# Relays.net
KiCad netlist of a schematic drawn in Altium Designer
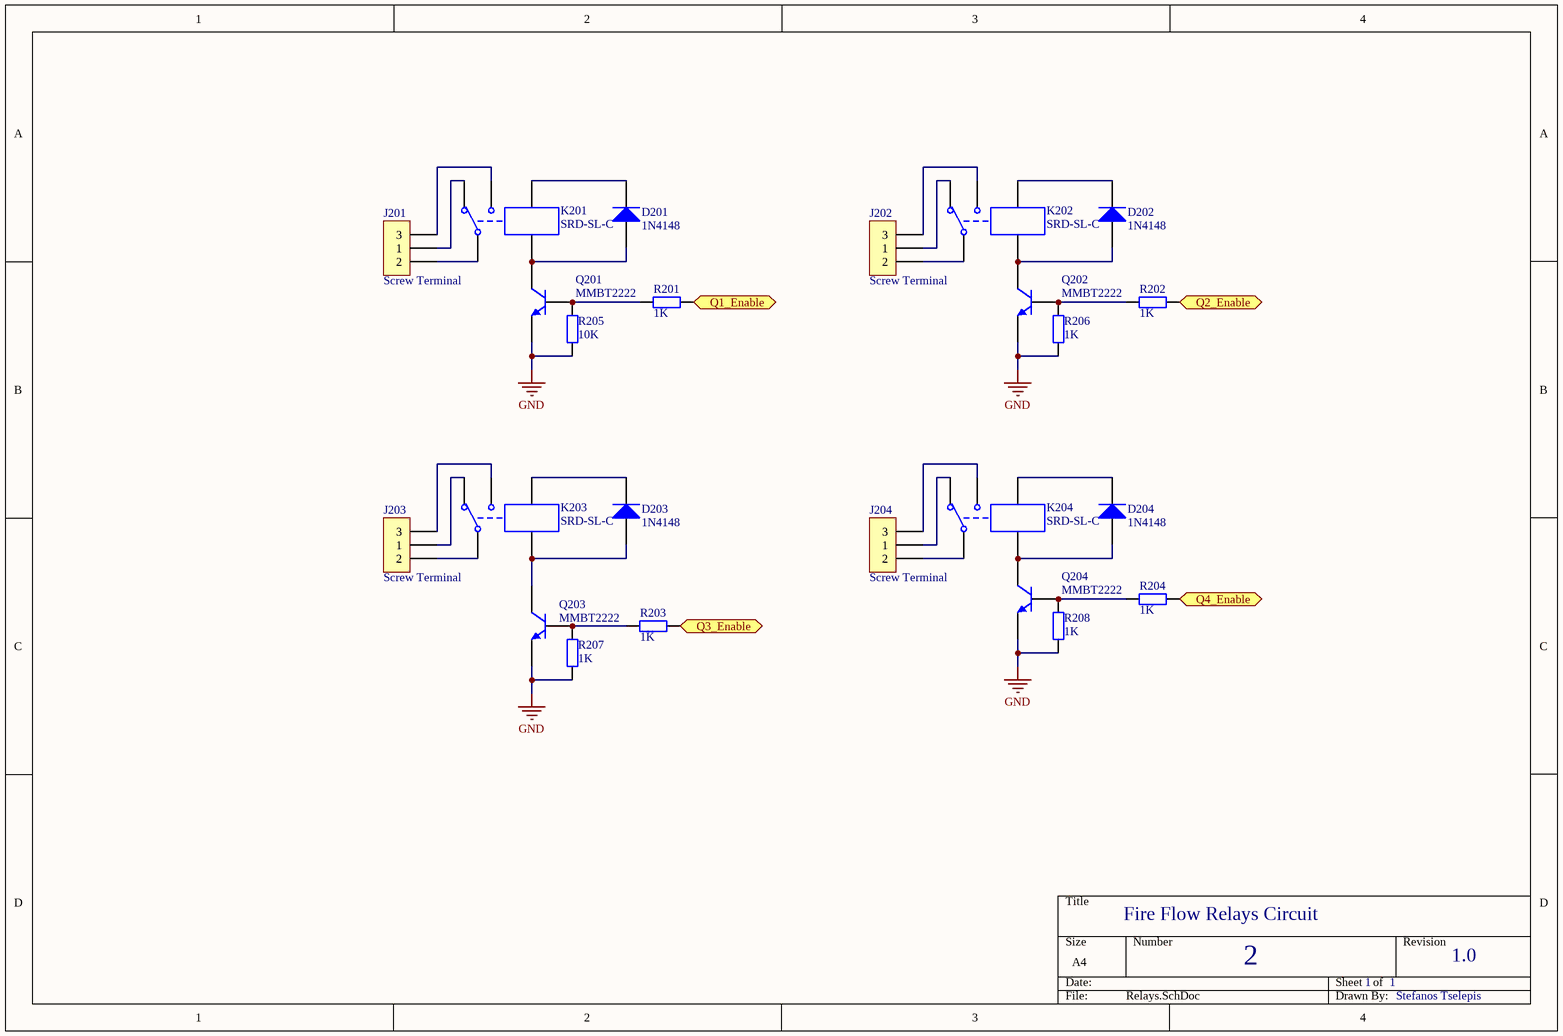
[diagram p0: Relays.SchDoc]

(export (version "E")
  (design (tool "Eeschema 10.0.6"))
  (components
    (comp (ref "D201")
      (value "1N4148")
      (footprint "CD2012-0805")
      (libsource (lib "FireFlow Lib") (part "Diode"))
    )
    (comp (ref "D202")
      (value "1N4148")
      (footprint "CD2012-0805")
      (libsource (lib "FireFlow Lib") (part "Diode"))
    )
    (comp (ref "D203")
      (value "1N4148")
      (footprint "CD2012-0805")
      (libsource (lib "FireFlow Lib") (part "Diode"))
    )
    (comp (ref "D204")
      (value "1N4148")
      (footprint "CD2012-0805")
      (libsource (lib "FireFlow Lib") (part "Diode"))
    )
    (comp (ref "J201")
      (value "Screw Terminal")
      (footprint "3pin ST")
      (description "WR-TBL Terminal block - serie 102 - 5.0mm")
      (libsource (lib "FireFlow Lib") (part "3 pin Screw Terminal"))
    )
    (comp (ref "J202")
      (value "Screw Terminal")
      (footprint "3pin ST")
      (description "WR-TBL Terminal block - serie 102 - 5.0mm")
      (libsource (lib "FireFlow Lib") (part "3 pin Screw Terminal"))
    )
    (comp (ref "J203")
      (value "Screw Terminal")
      (footprint "3pin ST")
      (description "WR-TBL Terminal block - serie 102 - 5.0mm")
      (libsource (lib "FireFlow Lib") (part "3 pin Screw Terminal"))
    )
    (comp (ref "J204")
      (value "Screw Terminal")
      (footprint "3pin ST")
      (description "WR-TBL Terminal block - serie 102 - 5.0mm")
      (libsource (lib "FireFlow Lib") (part "3 pin Screw Terminal"))
    )
    (comp (ref "K201")
      (value "SRD-SL-C")
      (footprint "SRD-SL-C")
      (libsource (lib "FireFlow") (part "Relay SRD-SL-C"))
    )
    (comp (ref "K202")
      (value "SRD-SL-C")
      (footprint "SRD-SL-C")
      (libsource (lib "FireFlow") (part "Relay SRD-SL-C"))
    )
    (comp (ref "K203")
      (value "SRD-SL-C")
      (footprint "SRD-SL-C")
      (libsource (lib "FireFlow") (part "Relay SRD-SL-C"))
    )
    (comp (ref "K204")
      (value "SRD-SL-C")
      (footprint "SRD-SL-C")
      (libsource (lib "FireFlow") (part "Relay SRD-SL-C"))
    )
    (comp (ref "Q201")
      (value "MMBT2222")
      (footprint "SO-G3")
      (description "NPN General Purpose Amplifier")
      (libsource (lib "FireFlow Lib") (part "MMBT2222"))
    )
    (comp (ref "Q202")
      (value "MMBT2222")
      (footprint "SO-G3")
      (description "NPN General Purpose Amplifier")
      (libsource (lib "FireFlow Lib") (part "MMBT2222"))
    )
    (comp (ref "Q203")
      (value "MMBT2222")
      (footprint "SO-G3")
      (description "NPN General Purpose Amplifier")
      (libsource (lib "FireFlow Lib") (part "MMBT2222"))
    )
    (comp (ref "Q204")
      (value "MMBT2222")
      (footprint "SO-G3")
      (description "NPN General Purpose Amplifier")
      (libsource (lib "FireFlow Lib") (part "MMBT2222"))
    )
    (comp (ref "R201") (value "1K") (footprint "CR2012-0805") (libsource (lib "") (part "Resistor_1")))
    (comp (ref "R202") (value "1K") (footprint "CR2012-0805") (libsource (lib "") (part "Resistor_1")))
    (comp (ref "R203") (value "1K") (footprint "CR2012-0805") (libsource (lib "") (part "Resistor_1")))
    (comp (ref "R204") (value "1K") (footprint "CR2012-0805") (libsource (lib "") (part "Resistor_1")))
    (comp (ref "R205")
      (value "10K")
      (footprint "CR2012-0805")
      (libsource (lib "FireFlow Lib") (part "Resistor"))
    )
    (comp (ref "R206")
      (value "1K")
      (footprint "CR2012-0805")
      (libsource (lib "FireFlow Lib") (part "Resistor"))
    )
    (comp (ref "R207")
      (value "1K")
      (footprint "CR2012-0805")
      (libsource (lib "FireFlow Lib") (part "Resistor"))
    )
    (comp (ref "R208")
      (value "1K")
      (footprint "CR2012-0805")
      (libsource (lib "FireFlow Lib") (part "Resistor"))
    )
  )
  (nets
    (net (code "1") (name "/Q1_Enable") (class "Default")
      (node (ref "R201") (pin "2") (pinfunction "2_2") (pintype "passive"))
    )
    (net (code "2") (name "/Q2_Enable") (class "Default")
      (node (ref "R202") (pin "2") (pinfunction "2_2") (pintype "passive"))
    )
    (net (code "3") (name "/Q3_Enable") (class "Default")
      (node (ref "R203") (pin "2") (pinfunction "2_2") (pintype "passive"))
    )
    (net (code "4") (name "/Q4_Enable") (class "Default")
      (node (ref "R204") (pin "2") (pinfunction "2_2") (pintype "passive"))
    )
    (net (code "5") (name "GND") (class "Default")
      (node (ref "Q201") (pin "2") (pinfunction "E_2") (pintype "passive"))
      (node (ref "Q202") (pin "2") (pinfunction "E_2") (pintype "passive"))
      (node (ref "Q203") (pin "2") (pinfunction "E_2") (pintype "passive"))
      (node (ref "Q204") (pin "2") (pinfunction "E_2") (pintype "passive"))
      (node (ref "R205") (pin "1") (pinfunction "1_1") (pintype "passive"))
      (node (ref "R206") (pin "1") (pinfunction "1_1") (pintype "passive"))
      (node (ref "R207") (pin "1") (pinfunction "1_1") (pintype "passive"))
      (node (ref "R208") (pin "1") (pinfunction "1_1") (pintype "passive"))
    )
    (net (code "6") (name "Net-(D201-PadK)") (class "Default")
      (node (ref "D201") (pin "K") (pinfunction "K_K") (pintype "passive"))
      (node (ref "K201") (pin "1") (pinfunction "1_1") (pintype "passive"))
    )
    (net (code "7") (name "Net-(D202-PadK)") (class "Default")
      (node (ref "D202") (pin "K") (pinfunction "K_K") (pintype "passive"))
      (node (ref "K202") (pin "1") (pinfunction "1_1") (pintype "passive"))
    )
    (net (code "8") (name "Net-(D203-PadK)") (class "Default")
      (node (ref "D203") (pin "K") (pinfunction "K_K") (pintype "passive"))
      (node (ref "K203") (pin "1") (pinfunction "1_1") (pintype "passive"))
    )
    (net (code "9") (name "Net-(D204-PadK)") (class "Default")
      (node (ref "D204") (pin "K") (pinfunction "K_K") (pintype "passive"))
      (node (ref "K204") (pin "1") (pinfunction "1_1") (pintype "passive"))
    )
    (net (code "10") (name "Net-(J201-Pad1)") (class "Default")
      (node (ref "J201") (pin "1") (pinfunction "1_1") (pintype "passive"))
      (node (ref "K201") (pin "5") (pinfunction "5_5") (pintype "passive"))
    )
    (net (code "11") (name "Net-(J201-Pad2)") (class "Default")
      (node (ref "J201") (pin "2") (pinfunction "2_2") (pintype "passive"))
      (node (ref "K201") (pin "3") (pinfunction "3_3") (pintype "passive"))
    )
    (net (code "12") (name "Net-(J201-Pad3)") (class "Default")
      (node (ref "J201") (pin "3") (pinfunction "3_3") (pintype "passive"))
      (node (ref "K201") (pin "4") (pinfunction "4_4") (pintype "passive"))
    )
    (net (code "13") (name "Net-(J202-Pad1)") (class "Default")
      (node (ref "J202") (pin "1") (pinfunction "1_1") (pintype "passive"))
      (node (ref "K202") (pin "5") (pinfunction "5_5") (pintype "passive"))
    )
    (net (code "14") (name "Net-(J202-Pad2)") (class "Default")
      (node (ref "J202") (pin "2") (pinfunction "2_2") (pintype "passive"))
      (node (ref "K202") (pin "3") (pinfunction "3_3") (pintype "passive"))
    )
    (net (code "15") (name "Net-(J202-Pad3)") (class "Default")
      (node (ref "J202") (pin "3") (pinfunction "3_3") (pintype "passive"))
      (node (ref "K202") (pin "4") (pinfunction "4_4") (pintype "passive"))
    )
    (net (code "16") (name "Net-(J203-Pad1)") (class "Default")
      (node (ref "J203") (pin "1") (pinfunction "1_1") (pintype "passive"))
      (node (ref "K203") (pin "5") (pinfunction "5_5") (pintype "passive"))
    )
    (net (code "17") (name "Net-(J203-Pad2)") (class "Default")
      (node (ref "J203") (pin "2") (pinfunction "2_2") (pintype "passive"))
      (node (ref "K203") (pin "3") (pinfunction "3_3") (pintype "passive"))
    )
    (net (code "18") (name "Net-(J203-Pad3)") (class "Default")
      (node (ref "J203") (pin "3") (pinfunction "3_3") (pintype "passive"))
      (node (ref "K203") (pin "4") (pinfunction "4_4") (pintype "passive"))
    )
    (net (code "19") (name "Net-(J204-Pad1)") (class "Default")
      (node (ref "J204") (pin "1") (pinfunction "1_1") (pintype "passive"))
      (node (ref "K204") (pin "5") (pinfunction "5_5") (pintype "passive"))
    )
    (net (code "20") (name "Net-(J204-Pad2)") (class "Default")
      (node (ref "J204") (pin "2") (pinfunction "2_2") (pintype "passive"))
      (node (ref "K204") (pin "3") (pinfunction "3_3") (pintype "passive"))
    )
    (net (code "21") (name "Net-(J204-Pad3)") (class "Default")
      (node (ref "J204") (pin "3") (pinfunction "3_3") (pintype "passive"))
      (node (ref "K204") (pin "4") (pinfunction "4_4") (pintype "passive"))
    )
    (net (code "22") (name "Net-(Q201-B)") (class "Default")
      (node (ref "Q201") (pin "1") (pinfunction "B_1") (pintype "passive"))
      (node (ref "R201") (pin "1") (pinfunction "1_1") (pintype "passive"))
      (node (ref "R205") (pin "2") (pinfunction "2_2") (pintype "passive"))
    )
    (net (code "23") (name "Net-(Q201-C)") (class "Default")
      (node (ref "D201") (pin "A") (pinfunction "A_A") (pintype "passive"))
      (node (ref "K201") (pin "2") (pinfunction "2_2") (pintype "passive"))
      (node (ref "Q201") (pin "3") (pinfunction "C_3") (pintype "passive"))
    )
    (net (code "24") (name "Net-(Q202-B)") (class "Default")
      (node (ref "Q202") (pin "1") (pinfunction "B_1") (pintype "passive"))
      (node (ref "R202") (pin "1") (pinfunction "1_1") (pintype "passive"))
      (node (ref "R206") (pin "2") (pinfunction "2_2") (pintype "passive"))
    )
    (net (code "25") (name "Net-(Q202-C)") (class "Default")
      (node (ref "D202") (pin "A") (pinfunction "A_A") (pintype "passive"))
      (node (ref "K202") (pin "2") (pinfunction "2_2") (pintype "passive"))
      (node (ref "Q202") (pin "3") (pinfunction "C_3") (pintype "passive"))
    )
    (net (code "26") (name "Net-(Q203-B)") (class "Default")
      (node (ref "Q203") (pin "1") (pinfunction "B_1") (pintype "passive"))
      (node (ref "R203") (pin "1") (pinfunction "1_1") (pintype "passive"))
      (node (ref "R207") (pin "2") (pinfunction "2_2") (pintype "passive"))
    )
    (net (code "27") (name "Net-(Q203-C)") (class "Default")
      (node (ref "D203") (pin "A") (pinfunction "A_A") (pintype "passive"))
      (node (ref "K203") (pin "2") (pinfunction "2_2") (pintype "passive"))
      (node (ref "Q203") (pin "3") (pinfunction "C_3") (pintype "passive"))
    )
    (net (code "28") (name "Net-(Q204-B)") (class "Default")
      (node (ref "Q204") (pin "1") (pinfunction "B_1") (pintype "passive"))
      (node (ref "R204") (pin "1") (pinfunction "1_1") (pintype "passive"))
      (node (ref "R208") (pin "2") (pinfunction "2_2") (pintype "passive"))
    )
    (net (code "29") (name "Net-(Q204-C)") (class "Default")
      (node (ref "D204") (pin "A") (pinfunction "A_A") (pintype "passive"))
      (node (ref "K204") (pin "2") (pinfunction "2_2") (pintype "passive"))
      (node (ref "Q204") (pin "3") (pinfunction "C_3") (pintype "passive"))
    )
  )
)
